# school.net
KiCad netlist of a schematic drawn in EasyEDA
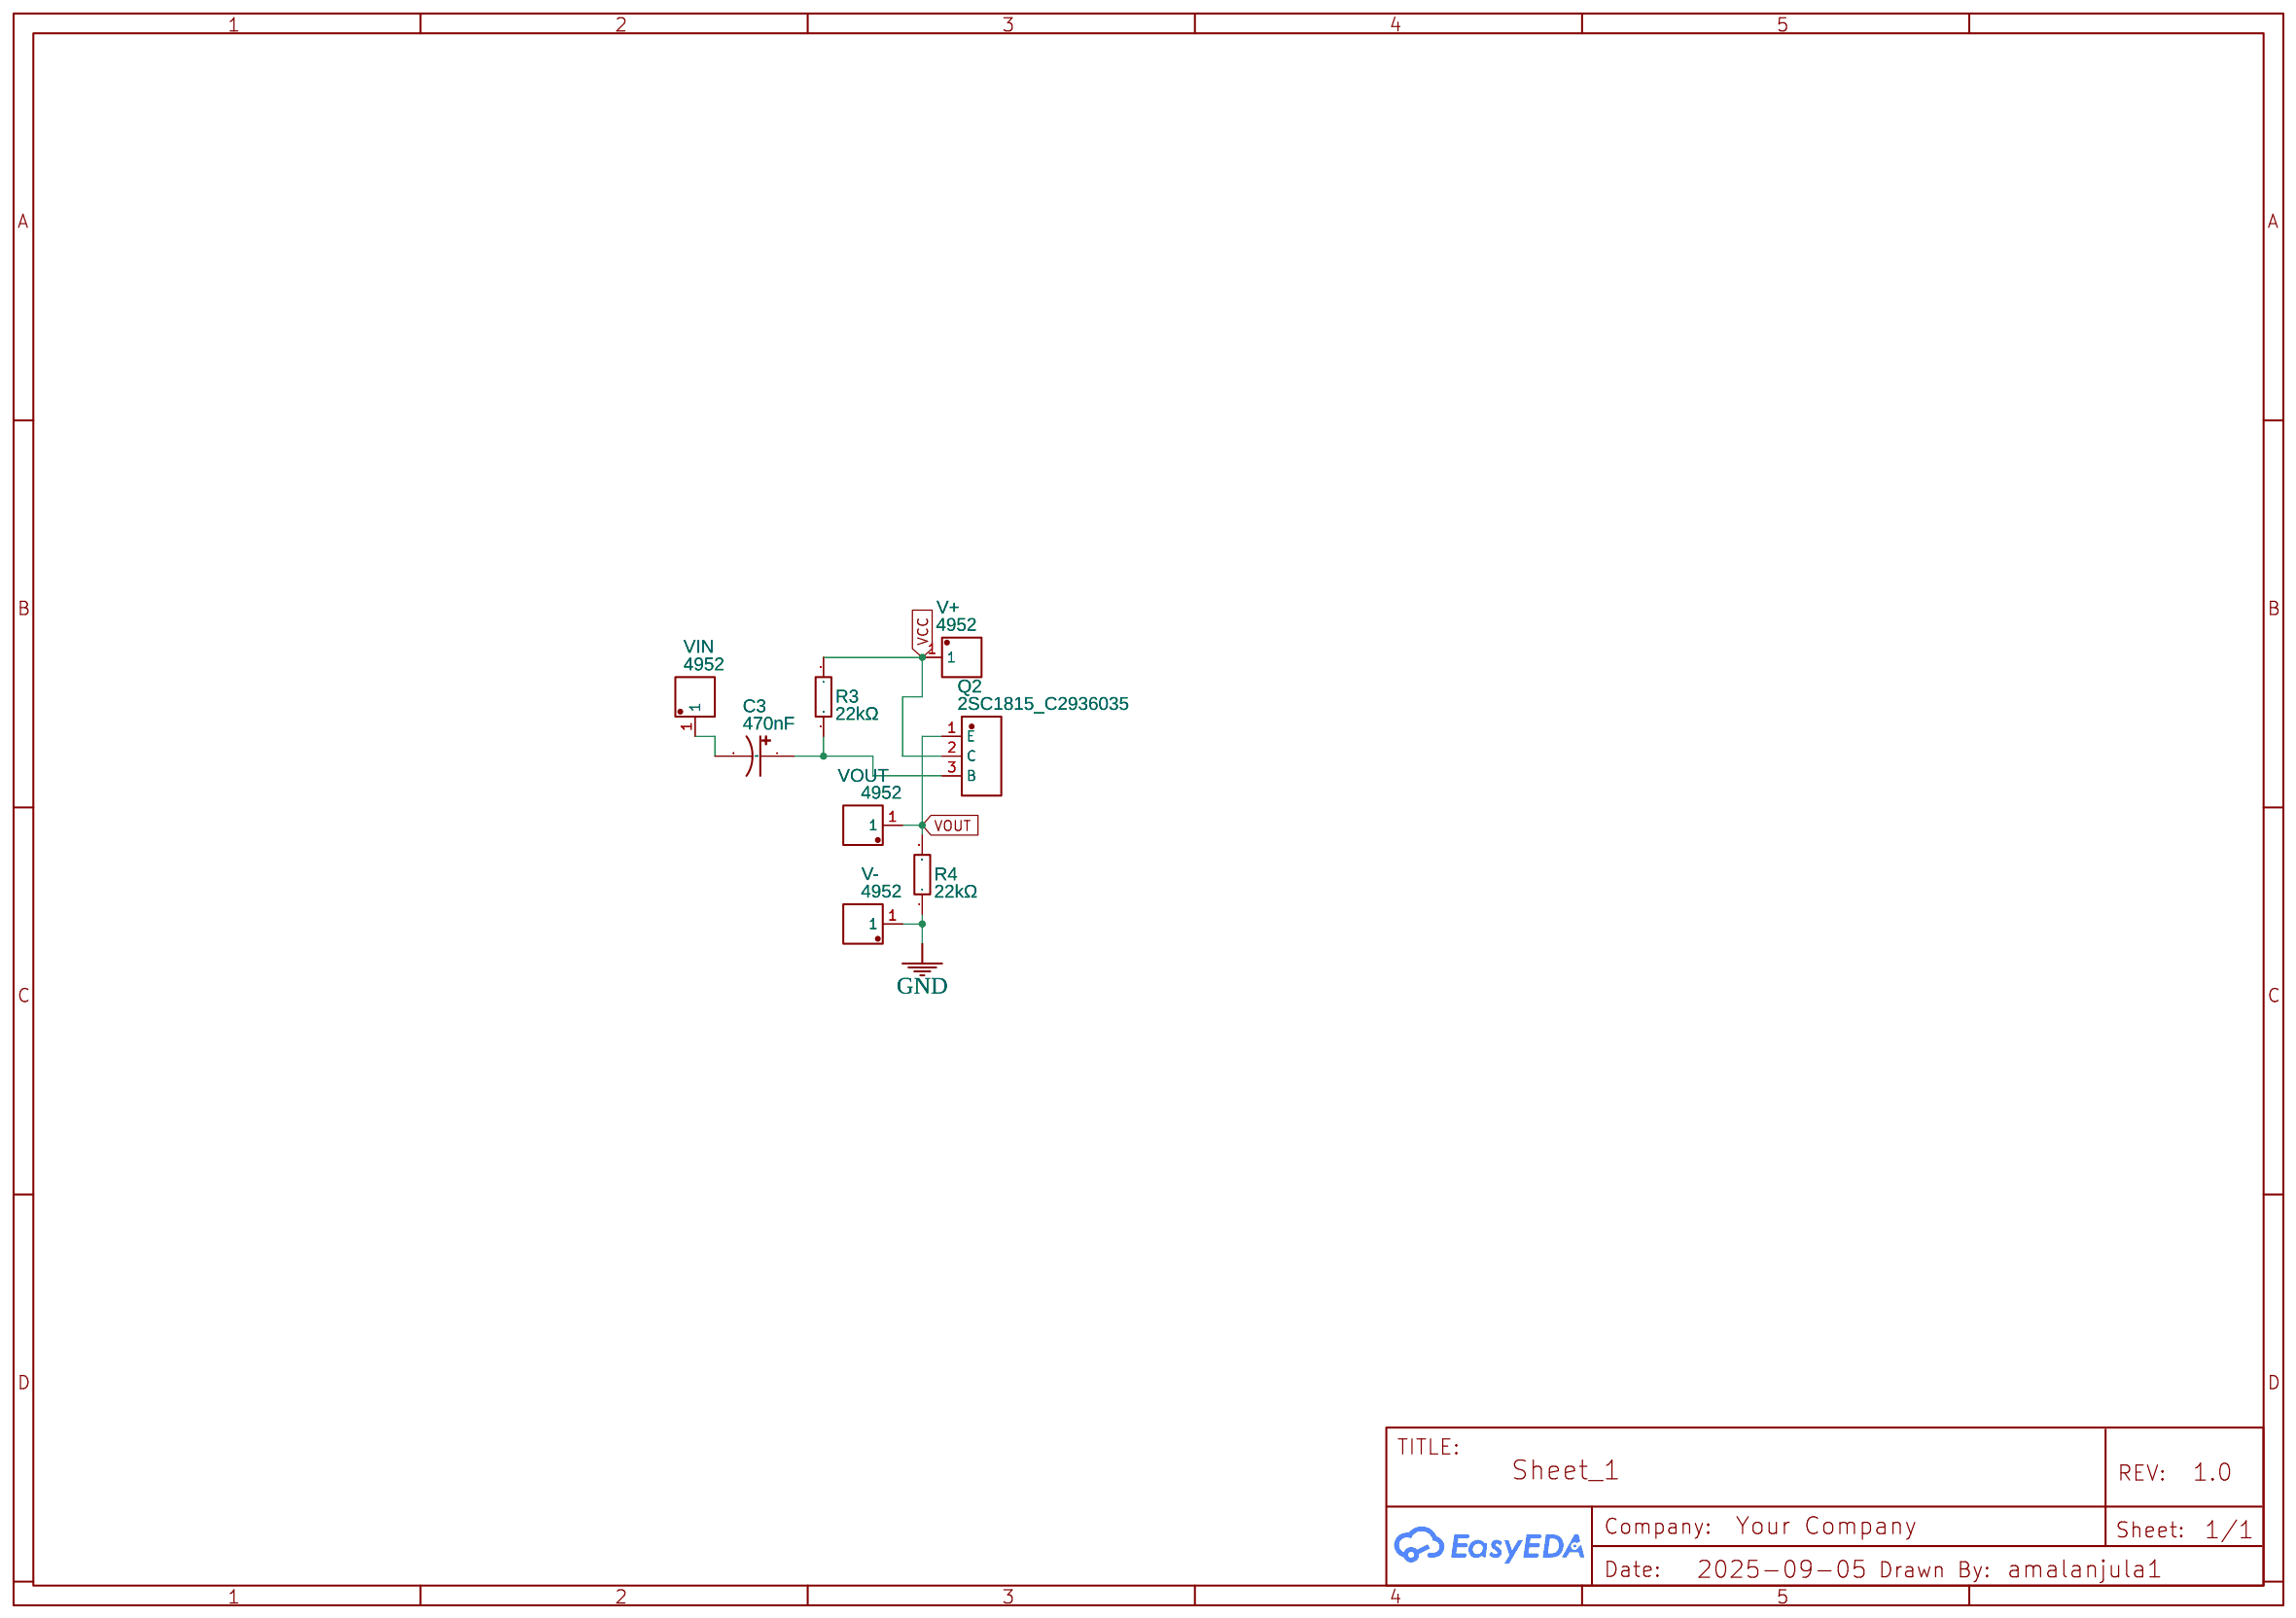
[diagram p0: schematic sheet]

(export (version "E")
  (design (tool "Eeschema 10.0.6"))
  (components
    (comp (ref "C3")
      (value "470nF")
      (fields (field (name "Manufacturer Part") "KMR47M050C110A") (field (name "Manufacturer") "CapXon(丰宾)"))
      (libsource (lib "") (part "KMR47M050C110A"))
    )
    (comp (ref "Q2")
      (value "2SC1815_C2936035")
      (fields (field (name "Manufacturer Part") "2SC1815") (field (name "Manufacturer") "Slkor(萨科微)"))
      (libsource (lib "") (part "2SC1815_C2936035"))
    )
    (comp (ref "R3")
      (value "22kΩ")
      (fields (field (name "Manufacturer Part") "MF1/4W-22KΩ±1% T") (field (name "Manufacturer") "CCO(千志电子)"))
      (libsource (lib "") (part "MF1/4W-22KΩ±1% T52"))
    )
    (comp (ref "R4")
      (value "22kΩ")
      (fields (field (name "Manufacturer Part") "MF1/4W-22KΩ±1% T") (field (name "Manufacturer") "CCO(千志电子)"))
      (libsource (lib "") (part "MF1/4W-22KΩ±1% T52"))
    )
    (comp (ref "V+")
      (value "4952")
      (fields (field (name "Manufacturer") "Keystone"))
      (libsource (lib "") (part "4952_1"))
    )
    (comp (ref "V-")
      (value "4952")
      (fields (field (name "Manufacturer") "Keystone"))
      (libsource (lib "") (part "4952"))
    )
    (comp (ref "VIN")
      (value "4952")
      (fields (field (name "Manufacturer") "Keystone"))
      (libsource (lib "") (part "4952_3"))
    )
    (comp (ref "VOUT")
      (value "4952")
      (fields (field (name "Manufacturer") "Keystone"))
      (libsource (lib "") (part "4952_2"))
    )
  )
  (nets
    (net (code "1") (name "GND") (class "Default")
      (node (ref "R4") (pin "1") (pinfunction "1_1") (pintype "unspecified"))
      (node (ref "V-") (pin "1") (pinfunction "1_1") (pintype "unspecified"))
    )
    (net (code "2") (name "Net-(C3-Pad2)") (class "Default")
      (node (ref "C3") (pin "2") (pinfunction "2_2") (pintype "unspecified"))
      (node (ref "VIN") (pin "1") (pinfunction "1_1") (pintype "unspecified"))
    )
    (net (code "3") (name "Net-(Q2-B)") (class "Default")
      (node (ref "C3") (pin "1") (pinfunction "1_1") (pintype "unspecified"))
      (node (ref "Q2") (pin "3") (pinfunction "B_3") (pintype "unspecified"))
      (node (ref "R3") (pin "1") (pinfunction "1_1") (pintype "unspecified"))
    )
    (net (code "4") (name "VCC") (class "Default")
      (node (ref "Q2") (pin "2") (pinfunction "C_2") (pintype "unspecified"))
      (node (ref "R3") (pin "2") (pinfunction "2_2") (pintype "unspecified"))
      (node (ref "V+") (pin "1") (pinfunction "1_1") (pintype "unspecified"))
    )
    (net (code "5") (name "VOUT") (class "Default")
      (node (ref "Q2") (pin "1") (pinfunction "E_1") (pintype "unspecified"))
      (node (ref "R4") (pin "2") (pinfunction "2_2") (pintype "unspecified"))
      (node (ref "VOUT") (pin "1") (pinfunction "1_1") (pintype "unspecified"))
    )
  )
)
